# Protoboard_MX4-7-9-ESP12.net
KiCad netlist of a schematic drawn in EAGLE
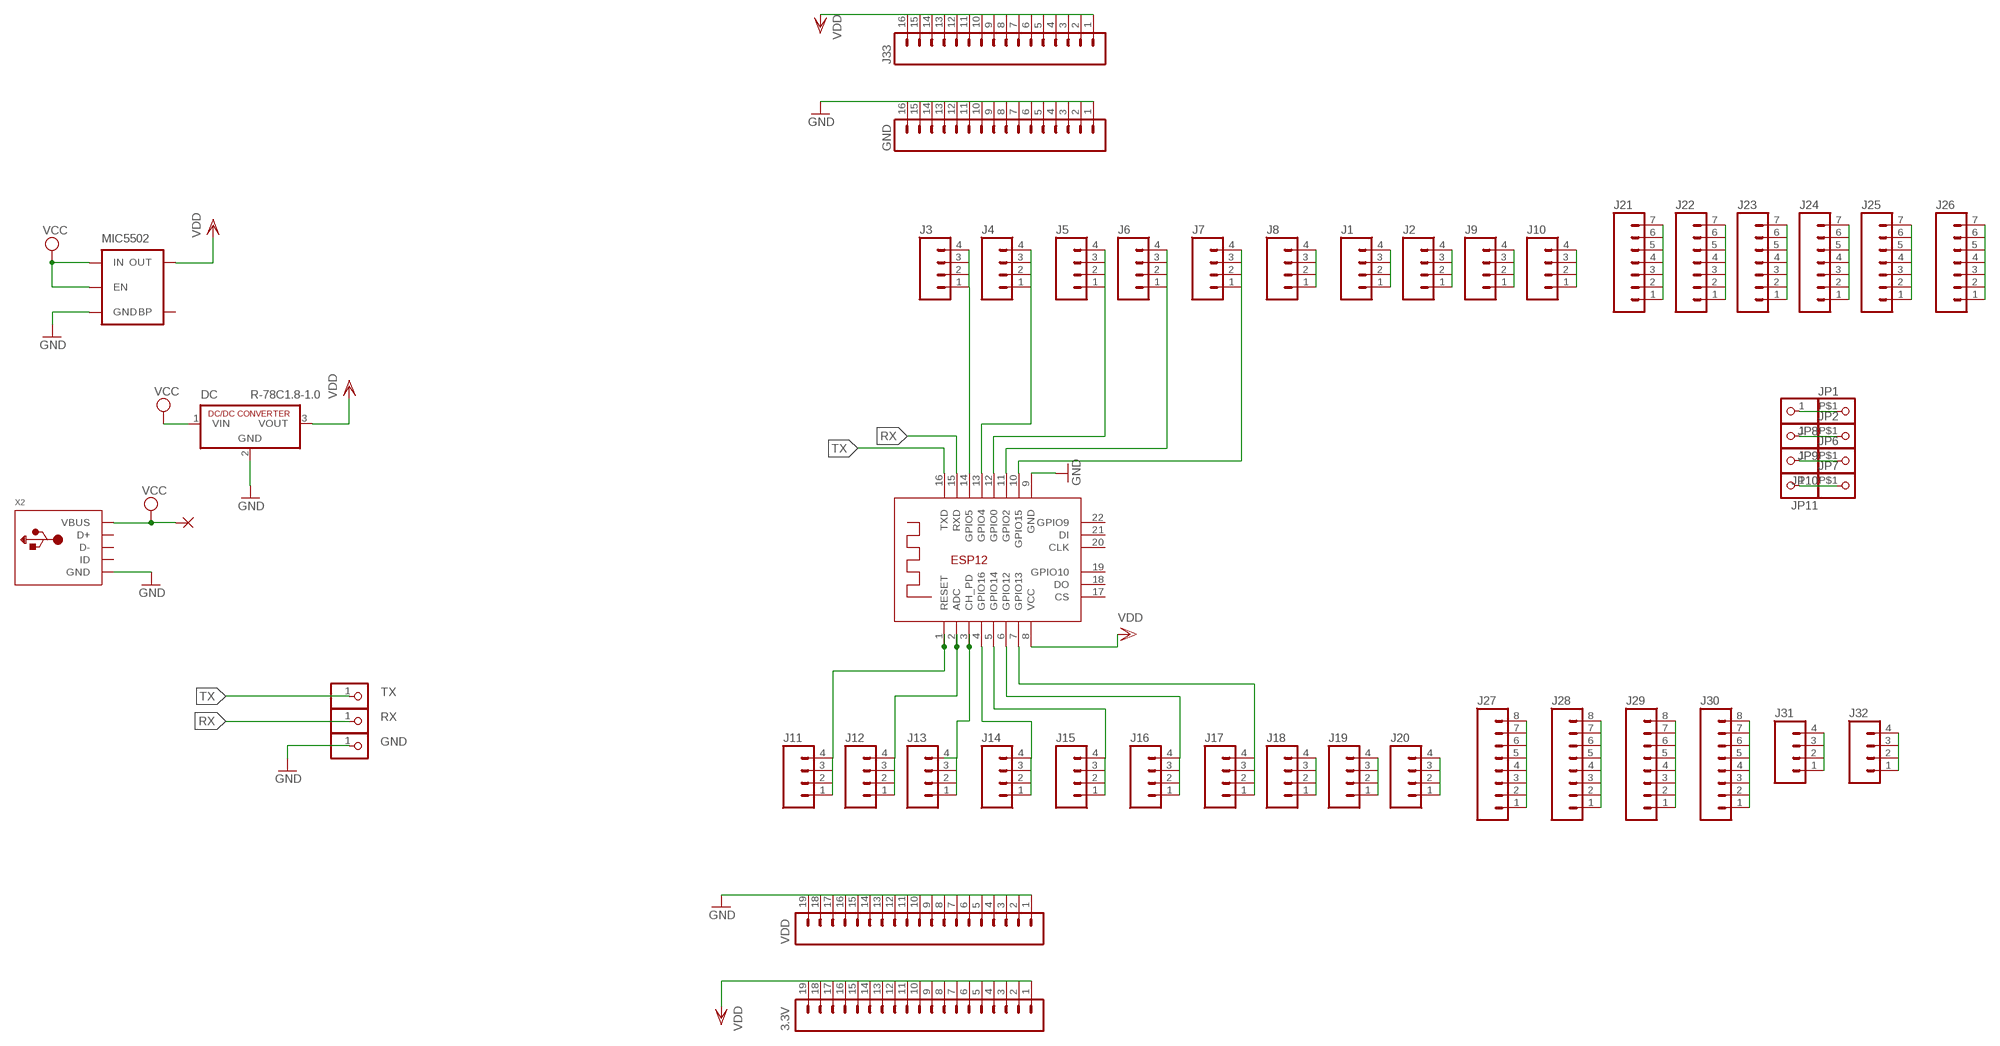
[diagram p0: schematic, sheet 1]

(export (version "E")
  (design (tool "Eeschema 10.0.6"))
  (components
    (comp (ref "3.3V")
      (value "M191X19_NO_SILK")
      (footprint "eagle-import:1X19_NO_SILK")
      (libsource (lib "eagle-import") (part "M191X19_NO_SILK"))
    )
    (comp (ref "5V")
      (value "1,6/0,8")
      (footprint "eagle-import:1,6_0,8")
      (libsource (lib "eagle-import") (part "1,6/0,8"))
    )
    (comp (ref "DC")
      (value "R-78C1.8-1.0")
      (footprint "eagle-import:SIP3")
      (libsource (lib "eagle-import") (part "R-78C-1.01.8"))
    )
    (comp (ref "GND")
      (value "M161X16_NO_SILK")
      (footprint "eagle-import:1X16_NO_SILK")
      (libsource (lib "eagle-import") (part "M161X16_NO_SILK"))
    )
    (comp (ref "J1")
      (value "M04NO_SILK_ALL_ROUND")
      (footprint "eagle-import:1X04_NO_SILK_ALL_ROUND")
      (libsource (lib "eagle-import") (part "M04NO_SILK_ALL_ROUND"))
    )
    (comp (ref "J2")
      (value "M04NO_SILK_ALL_ROUND")
      (footprint "eagle-import:1X04_NO_SILK_ALL_ROUND")
      (libsource (lib "eagle-import") (part "M04NO_SILK_ALL_ROUND"))
    )
    (comp (ref "J3")
      (value "M04NO_SILK_ALL_ROUND")
      (footprint "eagle-import:1X04_NO_SILK_ALL_ROUND")
      (libsource (lib "eagle-import") (part "M04NO_SILK_ALL_ROUND"))
    )
    (comp (ref "J4")
      (value "M04NO_SILK_ALL_ROUND")
      (footprint "eagle-import:1X04_NO_SILK_ALL_ROUND")
      (libsource (lib "eagle-import") (part "M04NO_SILK_ALL_ROUND"))
    )
    (comp (ref "J5")
      (value "M04NO_SILK_ALL_ROUND")
      (footprint "eagle-import:1X04_NO_SILK_ALL_ROUND")
      (libsource (lib "eagle-import") (part "M04NO_SILK_ALL_ROUND"))
    )
    (comp (ref "J6")
      (value "M04NO_SILK_ALL_ROUND")
      (footprint "eagle-import:1X04_NO_SILK_ALL_ROUND")
      (libsource (lib "eagle-import") (part "M04NO_SILK_ALL_ROUND"))
    )
    (comp (ref "J7")
      (value "M04NO_SILK_ALL_ROUND")
      (footprint "eagle-import:1X04_NO_SILK_ALL_ROUND")
      (libsource (lib "eagle-import") (part "M04NO_SILK_ALL_ROUND"))
    )
    (comp (ref "J8")
      (value "M04NO_SILK_ALL_ROUND")
      (footprint "eagle-import:1X04_NO_SILK_ALL_ROUND")
      (libsource (lib "eagle-import") (part "M04NO_SILK_ALL_ROUND"))
    )
    (comp (ref "J9")
      (value "M04NO_SILK_ALL_ROUND")
      (footprint "eagle-import:1X04_NO_SILK_ALL_ROUND")
      (libsource (lib "eagle-import") (part "M04NO_SILK_ALL_ROUND"))
    )
    (comp (ref "J10")
      (value "M04NO_SILK_ALL_ROUND")
      (footprint "eagle-import:1X04_NO_SILK_ALL_ROUND")
      (libsource (lib "eagle-import") (part "M04NO_SILK_ALL_ROUND"))
    )
    (comp (ref "J11")
      (value "M04NO_SILK_ALL_ROUND")
      (footprint "eagle-import:1X04_NO_SILK_ALL_ROUND")
      (libsource (lib "eagle-import") (part "M04NO_SILK_ALL_ROUND"))
    )
    (comp (ref "J12")
      (value "M04NO_SILK_ALL_ROUND")
      (footprint "eagle-import:1X04_NO_SILK_ALL_ROUND")
      (libsource (lib "eagle-import") (part "M04NO_SILK_ALL_ROUND"))
    )
    (comp (ref "J13")
      (value "M04NO_SILK_ALL_ROUND")
      (footprint "eagle-import:1X04_NO_SILK_ALL_ROUND")
      (libsource (lib "eagle-import") (part "M04NO_SILK_ALL_ROUND"))
    )
    (comp (ref "J14")
      (value "M04NO_SILK_ALL_ROUND")
      (footprint "eagle-import:1X04_NO_SILK_ALL_ROUND")
      (libsource (lib "eagle-import") (part "M04NO_SILK_ALL_ROUND"))
    )
    (comp (ref "J15")
      (value "M04NO_SILK_ALL_ROUND")
      (footprint "eagle-import:1X04_NO_SILK_ALL_ROUND")
      (libsource (lib "eagle-import") (part "M04NO_SILK_ALL_ROUND"))
    )
    (comp (ref "J16")
      (value "M04NO_SILK_ALL_ROUND")
      (footprint "eagle-import:1X04_NO_SILK_ALL_ROUND")
      (libsource (lib "eagle-import") (part "M04NO_SILK_ALL_ROUND"))
    )
    (comp (ref "J17")
      (value "M04NO_SILK_ALL_ROUND")
      (footprint "eagle-import:1X04_NO_SILK_ALL_ROUND")
      (libsource (lib "eagle-import") (part "M04NO_SILK_ALL_ROUND"))
    )
    (comp (ref "J18")
      (value "M04NO_SILK_ALL_ROUND")
      (footprint "eagle-import:1X04_NO_SILK_ALL_ROUND")
      (libsource (lib "eagle-import") (part "M04NO_SILK_ALL_ROUND"))
    )
    (comp (ref "J19")
      (value "M04NO_SILK_ALL_ROUND")
      (footprint "eagle-import:1X04_NO_SILK_ALL_ROUND")
      (libsource (lib "eagle-import") (part "M04NO_SILK_ALL_ROUND"))
    )
    (comp (ref "J20")
      (value "M04NO_SILK_ALL_ROUND")
      (footprint "eagle-import:1X04_NO_SILK_ALL_ROUND")
      (libsource (lib "eagle-import") (part "M04NO_SILK_ALL_ROUND"))
    )
    (comp (ref "J21")
      (value "M07NO_SILK")
      (footprint "eagle-import:1X07_NO_SILK")
      (libsource (lib "eagle-import") (part "M07NO_SILK"))
    )
    (comp (ref "J22")
      (value "M07NO_SILK")
      (footprint "eagle-import:1X07_NO_SILK")
      (libsource (lib "eagle-import") (part "M07NO_SILK"))
    )
    (comp (ref "J23")
      (value "M07NO_SILK")
      (footprint "eagle-import:1X07_NO_SILK")
      (libsource (lib "eagle-import") (part "M07NO_SILK"))
    )
    (comp (ref "J24")
      (value "M07NO_SILK")
      (footprint "eagle-import:1X07_NO_SILK")
      (libsource (lib "eagle-import") (part "M07NO_SILK"))
    )
    (comp (ref "J25")
      (value "M07NO_SILK")
      (footprint "eagle-import:1X07_NO_SILK")
      (libsource (lib "eagle-import") (part "M07NO_SILK"))
    )
    (comp (ref "J26")
      (value "M07NO_SILK")
      (footprint "eagle-import:1X07_NO_SILK")
      (libsource (lib "eagle-import") (part "M07NO_SILK"))
    )
    (comp (ref "J27")
      (value "M08NO_SILK_FEMALE_PTH")
      (footprint "eagle-import:1X08_NO_SILK")
      (libsource (lib "eagle-import") (part "M08NO_SILK_FEMALE_PTH"))
    )
    (comp (ref "J28")
      (value "M08NO_SILK_FEMALE_PTH")
      (footprint "eagle-import:1X08_NO_SILK")
      (libsource (lib "eagle-import") (part "M08NO_SILK_FEMALE_PTH"))
    )
    (comp (ref "J29")
      (value "M08NO_SILK_FEMALE_PTH")
      (footprint "eagle-import:1X08_NO_SILK")
      (libsource (lib "eagle-import") (part "M08NO_SILK_FEMALE_PTH"))
    )
    (comp (ref "J30")
      (value "M08NO_SILK_FEMALE_PTH")
      (footprint "eagle-import:1X08_NO_SILK")
      (libsource (lib "eagle-import") (part "M08NO_SILK_FEMALE_PTH"))
    )
    (comp (ref "J31")
      (value "M04NO_SILK_ALL_ROUND")
      (footprint "eagle-import:1X04_NO_SILK_ALL_ROUND")
      (libsource (lib "eagle-import") (part "M04NO_SILK_ALL_ROUND"))
    )
    (comp (ref "J32")
      (value "M04NO_SILK_ALL_ROUND")
      (footprint "eagle-import:1X04_NO_SILK_ALL_ROUND")
      (libsource (lib "eagle-import") (part "M04NO_SILK_ALL_ROUND"))
    )
    (comp (ref "J33")
      (value "M161X16_NO_SILK")
      (footprint "eagle-import:1X16_NO_SILK")
      (libsource (lib "eagle-import") (part "M161X16_NO_SILK"))
    )
    (comp (ref "JP1")
      (value "PINHD-1X1-BIGPOGO")
      (footprint "eagle-import:1X1-BIGPOGO")
      (libsource (lib "eagle-import") (part "PINHD-1X1-BIGPOGO"))
    )
    (comp (ref "JP2")
      (value "PINHD-1X1-BIGPOGO")
      (footprint "eagle-import:1X1-BIGPOGO")
      (libsource (lib "eagle-import") (part "PINHD-1X1-BIGPOGO"))
    )
    (comp (ref "JP3")
      (value "TX")
      (footprint "eagle-import:1X01-CLEANBIG")
      (libsource (lib "eagle-import") (part "PINHD-1X1CB"))
    )
    (comp (ref "JP4")
      (value "RX")
      (footprint "eagle-import:1X01-CLEANBIG")
      (libsource (lib "eagle-import") (part "PINHD-1X1CB"))
    )
    (comp (ref "JP5")
      (value "GND")
      (footprint "eagle-import:1X01-CLEANBIG")
      (libsource (lib "eagle-import") (part "PINHD-1X1CB"))
    )
    (comp (ref "JP6")
      (value "PINHD-1X1-BIGPOGO")
      (footprint "eagle-import:1X1-BIGPOGO")
      (libsource (lib "eagle-import") (part "PINHD-1X1-BIGPOGO"))
    )
    (comp (ref "JP7")
      (value "PINHD-1X1-BIGPOGO")
      (footprint "eagle-import:1X1-BIGPOGO")
      (libsource (lib "eagle-import") (part "PINHD-1X1-BIGPOGO"))
    )
    (comp (ref "JP8")
      (value "PINHD-1X1CB")
      (footprint "eagle-import:1X01-CLEANBIG")
      (libsource (lib "eagle-import") (part "PINHD-1X1CB"))
    )
    (comp (ref "JP9")
      (value "PINHD-1X1CB")
      (footprint "eagle-import:1X01-CLEANBIG")
      (libsource (lib "eagle-import") (part "PINHD-1X1CB"))
    )
    (comp (ref "JP10")
      (value "PINHD-1X1CB")
      (footprint "eagle-import:1X01-CLEANBIG")
      (libsource (lib "eagle-import") (part "PINHD-1X1CB"))
    )
    (comp (ref "JP11")
      (value "PINHD-1X1CB")
      (footprint "eagle-import:1X01-CLEANBIG")
      (libsource (lib "eagle-import") (part "PINHD-1X1CB"))
    )
    (comp (ref "MIC5502")
      (value "MIC52053.3V")
      (footprint "eagle-import:SOT23-5")
      (libsource (lib "eagle-import") (part "MIC52053.3V"))
    )
    (comp (ref "VDD")
      (value "M191X19_NO_SILK")
      (footprint "eagle-import:1X19_NO_SILK")
      (libsource (lib "eagle-import") (part "M191X19_NO_SILK"))
    )
    (comp (ref "X1")
      (value "ESP-12E")
      (footprint "eagle-import:ESP-12E")
      (libsource (lib "eagle-import") (part "ESP-12E"))
    )
    (comp (ref "X2")
      (value "USBMICRO_20329")
      (footprint "eagle-import:4UCONN_20329")
      (libsource (lib "eagle-import") (part "USBMICRO_20329"))
    )
  )
  (nets
    (net (code "1") (name "GND") (class "Default")
      (node (ref "DC") (pin "2") (pinfunction "GND_2") (pintype "passive"))
      (node (ref "GND") (pin "1") (pinfunction "1_1") (pintype "passive"))
      (node (ref "GND") (pin "10") (pinfunction "10_10") (pintype "passive"))
      (node (ref "GND") (pin "11") (pinfunction "11_11") (pintype "passive"))
      (node (ref "GND") (pin "12") (pinfunction "12_12") (pintype "passive"))
      (node (ref "GND") (pin "13") (pinfunction "13_13") (pintype "passive"))
      (node (ref "GND") (pin "14") (pinfunction "14_14") (pintype "passive"))
      (node (ref "GND") (pin "15") (pinfunction "15_15") (pintype "passive"))
      (node (ref "GND") (pin "16") (pinfunction "16_16") (pintype "passive"))
      (node (ref "GND") (pin "2") (pinfunction "2_2") (pintype "passive"))
      (node (ref "GND") (pin "3") (pinfunction "3_3") (pintype "passive"))
      (node (ref "GND") (pin "4") (pinfunction "4_4") (pintype "passive"))
      (node (ref "GND") (pin "5") (pinfunction "5_5") (pintype "passive"))
      (node (ref "GND") (pin "6") (pinfunction "6_6") (pintype "passive"))
      (node (ref "GND") (pin "7") (pinfunction "7_7") (pintype "passive"))
      (node (ref "GND") (pin "8") (pinfunction "8_8") (pintype "passive"))
      (node (ref "GND") (pin "9") (pinfunction "9_9") (pintype "passive"))
      (node (ref "JP5") (pin "1") (pinfunction "1_1") (pintype "passive"))
      (node (ref "MIC5502") (pin "2") (pinfunction "GND_2") (pintype "input"))
      (node (ref "VDD") (pin "1") (pinfunction "1_1") (pintype "passive"))
      (node (ref "VDD") (pin "10") (pinfunction "10_10") (pintype "passive"))
      (node (ref "VDD") (pin "11") (pinfunction "11_11") (pintype "passive"))
      (node (ref "VDD") (pin "12") (pinfunction "12_12") (pintype "passive"))
      (node (ref "VDD") (pin "13") (pinfunction "13_13") (pintype "passive"))
      (node (ref "VDD") (pin "14") (pinfunction "14_14") (pintype "passive"))
      (node (ref "VDD") (pin "15") (pinfunction "15_15") (pintype "passive"))
      (node (ref "VDD") (pin "16") (pinfunction "16_16") (pintype "passive"))
      (node (ref "VDD") (pin "17") (pinfunction "17_17") (pintype "passive"))
      (node (ref "VDD") (pin "18") (pinfunction "18_18") (pintype "passive"))
      (node (ref "VDD") (pin "19") (pinfunction "19_19") (pintype "passive"))
      (node (ref "VDD") (pin "2") (pinfunction "2_2") (pintype "passive"))
      (node (ref "VDD") (pin "3") (pinfunction "3_3") (pintype "passive"))
      (node (ref "VDD") (pin "4") (pinfunction "4_4") (pintype "passive"))
      (node (ref "VDD") (pin "5") (pinfunction "5_5") (pintype "passive"))
      (node (ref "VDD") (pin "6") (pinfunction "6_6") (pintype "passive"))
      (node (ref "VDD") (pin "7") (pinfunction "7_7") (pintype "passive"))
      (node (ref "VDD") (pin "8") (pinfunction "8_8") (pintype "passive"))
      (node (ref "VDD") (pin "9") (pinfunction "9_9") (pintype "passive"))
      (node (ref "X1") (pin "9") (pinfunction "GND_9") (pintype "power_in"))
      (node (ref "X2") (pin "BASE@1") (pinfunction "GND_BASE@1") (pintype "power_in"))
      (node (ref "X2") (pin "BASE@2") (pinfunction "GND_BASE@2") (pintype "power_in"))
      (node (ref "X2") (pin "GND") (pinfunction "GND_GND") (pintype "power_in"))
      (node (ref "X2") (pin "SPRT@1") (pinfunction "GND_SPRT@1") (pintype "power_in"))
      (node (ref "X2") (pin "SPRT@2") (pinfunction "GND_SPRT@2") (pintype "power_in"))
      (node (ref "X2") (pin "SPRT@3") (pinfunction "GND_SPRT@3") (pintype "power_in"))
      (node (ref "X2") (pin "SPRT@4") (pinfunction "GND_SPRT@4") (pintype "power_in"))
    )
    (net (code "2") (name "Net-(J1-Pad1)") (class "Default")
      (node (ref "J1") (pin "1") (pinfunction "1_1") (pintype "passive"))
      (node (ref "J1") (pin "2") (pinfunction "2_2") (pintype "passive"))
      (node (ref "J1") (pin "3") (pinfunction "3_3") (pintype "passive"))
      (node (ref "J1") (pin "4") (pinfunction "4_4") (pintype "passive"))
    )
    (net (code "3") (name "Net-(J2-Pad1)") (class "Default")
      (node (ref "J2") (pin "1") (pinfunction "1_1") (pintype "passive"))
      (node (ref "J2") (pin "2") (pinfunction "2_2") (pintype "passive"))
      (node (ref "J2") (pin "3") (pinfunction "3_3") (pintype "passive"))
      (node (ref "J2") (pin "4") (pinfunction "4_4") (pintype "passive"))
    )
    (net (code "4") (name "Net-(J8-Pad1)") (class "Default")
      (node (ref "J8") (pin "1") (pinfunction "1_1") (pintype "passive"))
      (node (ref "J8") (pin "2") (pinfunction "2_2") (pintype "passive"))
      (node (ref "J8") (pin "3") (pinfunction "3_3") (pintype "passive"))
      (node (ref "J8") (pin "4") (pinfunction "4_4") (pintype "passive"))
    )
    (net (code "5") (name "Net-(J9-Pad1)") (class "Default")
      (node (ref "J9") (pin "1") (pinfunction "1_1") (pintype "passive"))
      (node (ref "J9") (pin "2") (pinfunction "2_2") (pintype "passive"))
      (node (ref "J9") (pin "3") (pinfunction "3_3") (pintype "passive"))
      (node (ref "J9") (pin "4") (pinfunction "4_4") (pintype "passive"))
    )
    (net (code "6") (name "Net-(J10-Pad1)") (class "Default")
      (node (ref "J10") (pin "1") (pinfunction "1_1") (pintype "passive"))
      (node (ref "J10") (pin "2") (pinfunction "2_2") (pintype "passive"))
      (node (ref "J10") (pin "3") (pinfunction "3_3") (pintype "passive"))
      (node (ref "J10") (pin "4") (pinfunction "4_4") (pintype "passive"))
    )
    (net (code "7") (name "Net-(J18-Pad1)") (class "Default")
      (node (ref "J18") (pin "1") (pinfunction "1_1") (pintype "passive"))
      (node (ref "J18") (pin "2") (pinfunction "2_2") (pintype "passive"))
      (node (ref "J18") (pin "3") (pinfunction "3_3") (pintype "passive"))
      (node (ref "J18") (pin "4") (pinfunction "4_4") (pintype "passive"))
    )
    (net (code "8") (name "Net-(J19-Pad1)") (class "Default")
      (node (ref "J19") (pin "1") (pinfunction "1_1") (pintype "passive"))
      (node (ref "J19") (pin "2") (pinfunction "2_2") (pintype "passive"))
      (node (ref "J19") (pin "3") (pinfunction "3_3") (pintype "passive"))
      (node (ref "J19") (pin "4") (pinfunction "4_4") (pintype "passive"))
    )
    (net (code "9") (name "Net-(J20-Pad1)") (class "Default")
      (node (ref "J20") (pin "1") (pinfunction "1_1") (pintype "passive"))
      (node (ref "J20") (pin "2") (pinfunction "2_2") (pintype "passive"))
      (node (ref "J20") (pin "3") (pinfunction "3_3") (pintype "passive"))
      (node (ref "J20") (pin "4") (pinfunction "4_4") (pintype "passive"))
    )
    (net (code "10") (name "Net-(J21-Pad1)") (class "Default")
      (node (ref "J21") (pin "1") (pinfunction "1_1") (pintype "passive"))
      (node (ref "J21") (pin "2") (pinfunction "2_2") (pintype "passive"))
      (node (ref "J21") (pin "3") (pinfunction "3_3") (pintype "passive"))
      (node (ref "J21") (pin "4") (pinfunction "4_4") (pintype "passive"))
      (node (ref "J21") (pin "5") (pinfunction "5_5") (pintype "passive"))
      (node (ref "J21") (pin "6") (pinfunction "6_6") (pintype "passive"))
      (node (ref "J21") (pin "7") (pinfunction "7_7") (pintype "passive"))
    )
    (net (code "11") (name "Net-(J22-Pad1)") (class "Default")
      (node (ref "J22") (pin "1") (pinfunction "1_1") (pintype "passive"))
      (node (ref "J22") (pin "2") (pinfunction "2_2") (pintype "passive"))
      (node (ref "J22") (pin "3") (pinfunction "3_3") (pintype "passive"))
      (node (ref "J22") (pin "4") (pinfunction "4_4") (pintype "passive"))
      (node (ref "J22") (pin "5") (pinfunction "5_5") (pintype "passive"))
      (node (ref "J22") (pin "6") (pinfunction "6_6") (pintype "passive"))
      (node (ref "J22") (pin "7") (pinfunction "7_7") (pintype "passive"))
    )
    (net (code "12") (name "Net-(J23-Pad1)") (class "Default")
      (node (ref "J23") (pin "1") (pinfunction "1_1") (pintype "passive"))
      (node (ref "J23") (pin "2") (pinfunction "2_2") (pintype "passive"))
      (node (ref "J23") (pin "3") (pinfunction "3_3") (pintype "passive"))
      (node (ref "J23") (pin "4") (pinfunction "4_4") (pintype "passive"))
      (node (ref "J23") (pin "5") (pinfunction "5_5") (pintype "passive"))
      (node (ref "J23") (pin "6") (pinfunction "6_6") (pintype "passive"))
      (node (ref "J23") (pin "7") (pinfunction "7_7") (pintype "passive"))
    )
    (net (code "13") (name "Net-(J24-Pad1)") (class "Default")
      (node (ref "J24") (pin "1") (pinfunction "1_1") (pintype "passive"))
      (node (ref "J24") (pin "2") (pinfunction "2_2") (pintype "passive"))
      (node (ref "J24") (pin "3") (pinfunction "3_3") (pintype "passive"))
      (node (ref "J24") (pin "4") (pinfunction "4_4") (pintype "passive"))
      (node (ref "J24") (pin "5") (pinfunction "5_5") (pintype "passive"))
      (node (ref "J24") (pin "6") (pinfunction "6_6") (pintype "passive"))
      (node (ref "J24") (pin "7") (pinfunction "7_7") (pintype "passive"))
    )
    (net (code "14") (name "Net-(J25-Pad1)") (class "Default")
      (node (ref "J25") (pin "1") (pinfunction "1_1") (pintype "passive"))
      (node (ref "J25") (pin "2") (pinfunction "2_2") (pintype "passive"))
      (node (ref "J25") (pin "3") (pinfunction "3_3") (pintype "passive"))
      (node (ref "J25") (pin "4") (pinfunction "4_4") (pintype "passive"))
      (node (ref "J25") (pin "5") (pinfunction "5_5") (pintype "passive"))
      (node (ref "J25") (pin "6") (pinfunction "6_6") (pintype "passive"))
      (node (ref "J25") (pin "7") (pinfunction "7_7") (pintype "passive"))
    )
    (net (code "15") (name "Net-(J26-Pad1)") (class "Default")
      (node (ref "J26") (pin "1") (pinfunction "1_1") (pintype "passive"))
      (node (ref "J26") (pin "2") (pinfunction "2_2") (pintype "passive"))
      (node (ref "J26") (pin "3") (pinfunction "3_3") (pintype "passive"))
      (node (ref "J26") (pin "4") (pinfunction "4_4") (pintype "passive"))
      (node (ref "J26") (pin "5") (pinfunction "5_5") (pintype "passive"))
      (node (ref "J26") (pin "6") (pinfunction "6_6") (pintype "passive"))
      (node (ref "J26") (pin "7") (pinfunction "7_7") (pintype "passive"))
    )
    (net (code "16") (name "Net-(J27-Pad1)") (class "Default")
      (node (ref "J27") (pin "1") (pinfunction "1_1") (pintype "passive"))
      (node (ref "J27") (pin "2") (pinfunction "2_2") (pintype "passive"))
      (node (ref "J27") (pin "3") (pinfunction "3_3") (pintype "passive"))
      (node (ref "J27") (pin "4") (pinfunction "4_4") (pintype "passive"))
      (node (ref "J27") (pin "5") (pinfunction "5_5") (pintype "passive"))
      (node (ref "J27") (pin "6") (pinfunction "6_6") (pintype "passive"))
      (node (ref "J27") (pin "7") (pinfunction "7_7") (pintype "passive"))
      (node (ref "J27") (pin "8") (pinfunction "8_8") (pintype "passive"))
    )
    (net (code "17") (name "Net-(J28-Pad1)") (class "Default")
      (node (ref "J28") (pin "1") (pinfunction "1_1") (pintype "passive"))
      (node (ref "J28") (pin "2") (pinfunction "2_2") (pintype "passive"))
      (node (ref "J28") (pin "3") (pinfunction "3_3") (pintype "passive"))
      (node (ref "J28") (pin "4") (pinfunction "4_4") (pintype "passive"))
      (node (ref "J28") (pin "5") (pinfunction "5_5") (pintype "passive"))
      (node (ref "J28") (pin "6") (pinfunction "6_6") (pintype "passive"))
      (node (ref "J28") (pin "7") (pinfunction "7_7") (pintype "passive"))
      (node (ref "J28") (pin "8") (pinfunction "8_8") (pintype "passive"))
    )
    (net (code "18") (name "Net-(J29-Pad1)") (class "Default")
      (node (ref "J29") (pin "1") (pinfunction "1_1") (pintype "passive"))
      (node (ref "J29") (pin "2") (pinfunction "2_2") (pintype "passive"))
      (node (ref "J29") (pin "3") (pinfunction "3_3") (pintype "passive"))
      (node (ref "J29") (pin "4") (pinfunction "4_4") (pintype "passive"))
      (node (ref "J29") (pin "5") (pinfunction "5_5") (pintype "passive"))
      (node (ref "J29") (pin "6") (pinfunction "6_6") (pintype "passive"))
      (node (ref "J29") (pin "7") (pinfunction "7_7") (pintype "passive"))
      (node (ref "J29") (pin "8") (pinfunction "8_8") (pintype "passive"))
    )
    (net (code "19") (name "Net-(J30-Pad1)") (class "Default")
      (node (ref "J30") (pin "1") (pinfunction "1_1") (pintype "passive"))
      (node (ref "J30") (pin "2") (pinfunction "2_2") (pintype "passive"))
      (node (ref "J30") (pin "3") (pinfunction "3_3") (pintype "passive"))
      (node (ref "J30") (pin "4") (pinfunction "4_4") (pintype "passive"))
      (node (ref "J30") (pin "5") (pinfunction "5_5") (pintype "passive"))
      (node (ref "J30") (pin "6") (pinfunction "6_6") (pintype "passive"))
      (node (ref "J30") (pin "7") (pinfunction "7_7") (pintype "passive"))
      (node (ref "J30") (pin "8") (pinfunction "8_8") (pintype "passive"))
    )
    (net (code "20") (name "Net-(J31-Pad1)") (class "Default")
      (node (ref "J31") (pin "1") (pinfunction "1_1") (pintype "passive"))
      (node (ref "J31") (pin "2") (pinfunction "2_2") (pintype "passive"))
      (node (ref "J31") (pin "3") (pinfunction "3_3") (pintype "passive"))
      (node (ref "J31") (pin "4") (pinfunction "4_4") (pintype "passive"))
    )
    (net (code "21") (name "Net-(J32-Pad1)") (class "Default")
      (node (ref "J32") (pin "1") (pinfunction "1_1") (pintype "passive"))
      (node (ref "J32") (pin "2") (pinfunction "2_2") (pintype "passive"))
      (node (ref "J32") (pin "3") (pinfunction "3_3") (pintype "passive"))
      (node (ref "J32") (pin "4") (pinfunction "4_4") (pintype "passive"))
    )
    (net (code "22") (name "Net-(JP1-1)") (class "Default")
      (node (ref "JP1") (pin "P$1") (pinfunction "1_P$1") (pintype "passive"))
      (node (ref "JP8") (pin "1") (pinfunction "1_1") (pintype "passive"))
    )
    (net (code "23") (name "Net-(JP2-1)") (class "Default")
      (node (ref "JP2") (pin "P$1") (pinfunction "1_P$1") (pintype "passive"))
      (node (ref "JP9") (pin "1") (pinfunction "1_1") (pintype "passive"))
    )
    (net (code "24") (name "Net-(JP6-1)") (class "Default")
      (node (ref "JP10") (pin "1") (pinfunction "1_1") (pintype "passive"))
      (node (ref "JP6") (pin "P$1") (pinfunction "1_P$1") (pintype "passive"))
    )
    (net (code "25") (name "Net-(JP7-1)") (class "Default")
      (node (ref "JP11") (pin "1") (pinfunction "1_1") (pintype "passive"))
      (node (ref "JP7") (pin "P$1") (pinfunction "1_P$1") (pintype "passive"))
    )
    (net (code "26") (name "Net-(X1-ADC)") (class "Default")
      (node (ref "J12") (pin "1") (pinfunction "1_1") (pintype "passive"))
      (node (ref "J12") (pin "2") (pinfunction "2_2") (pintype "passive"))
      (node (ref "J12") (pin "3") (pinfunction "3_3") (pintype "passive"))
      (node (ref "J12") (pin "4") (pinfunction "4_4") (pintype "passive"))
      (node (ref "X1") (pin "2") (pinfunction "ADC_2") (pintype "passive"))
    )
    (net (code "27") (name "Net-(X1-CH_PD)") (class "Default")
      (node (ref "J13") (pin "1") (pinfunction "1_1") (pintype "passive"))
      (node (ref "J13") (pin "2") (pinfunction "2_2") (pintype "passive"))
      (node (ref "J13") (pin "3") (pinfunction "3_3") (pintype "passive"))
      (node (ref "J13") (pin "4") (pinfunction "4_4") (pintype "passive"))
      (node (ref "X1") (pin "3") (pinfunction "CH_PD_3") (pintype "input"))
    )
    (net (code "28") (name "Net-(X1-GPIO0)") (class "Default")
      (node (ref "J5") (pin "1") (pinfunction "1_1") (pintype "passive"))
      (node (ref "J5") (pin "2") (pinfunction "2_2") (pintype "passive"))
      (node (ref "J5") (pin "3") (pinfunction "3_3") (pintype "passive"))
      (node (ref "J5") (pin "4") (pinfunction "4_4") (pintype "passive"))
      (node (ref "X1") (pin "12") (pinfunction "GPIO0_12") (pintype "bidirectional"))
    )
    (net (code "29") (name "Net-(X1-GPIO2)") (class "Default")
      (node (ref "J6") (pin "1") (pinfunction "1_1") (pintype "passive"))
      (node (ref "J6") (pin "2") (pinfunction "2_2") (pintype "passive"))
      (node (ref "J6") (pin "3") (pinfunction "3_3") (pintype "passive"))
      (node (ref "J6") (pin "4") (pinfunction "4_4") (pintype "passive"))
      (node (ref "X1") (pin "11") (pinfunction "GPIO2_11") (pintype "bidirectional"))
    )
    (net (code "30") (name "Net-(X1-GPIO4)") (class "Default")
      (node (ref "J4") (pin "1") (pinfunction "1_1") (pintype "passive"))
      (node (ref "J4") (pin "2") (pinfunction "2_2") (pintype "passive"))
      (node (ref "J4") (pin "3") (pinfunction "3_3") (pintype "passive"))
      (node (ref "J4") (pin "4") (pinfunction "4_4") (pintype "passive"))
      (node (ref "X1") (pin "13") (pinfunction "GPIO4_13") (pintype "bidirectional"))
    )
    (net (code "31") (name "Net-(X1-GPIO5)") (class "Default")
      (node (ref "J3") (pin "1") (pinfunction "1_1") (pintype "passive"))
      (node (ref "J3") (pin "2") (pinfunction "2_2") (pintype "passive"))
      (node (ref "J3") (pin "3") (pinfunction "3_3") (pintype "passive"))
      (node (ref "J3") (pin "4") (pinfunction "4_4") (pintype "passive"))
      (node (ref "X1") (pin "14") (pinfunction "GPIO5_14") (pintype "bidirectional"))
    )
    (net (code "32") (name "Net-(X1-GPIO12)") (class "Default")
      (node (ref "J16") (pin "1") (pinfunction "1_1") (pintype "passive"))
      (node (ref "J16") (pin "2") (pinfunction "2_2") (pintype "passive"))
      (node (ref "J16") (pin "3") (pinfunction "3_3") (pintype "passive"))
      (node (ref "J16") (pin "4") (pinfunction "4_4") (pintype "passive"))
      (node (ref "X1") (pin "6") (pinfunction "GPIO12_6") (pintype "bidirectional"))
    )
    (net (code "33") (name "Net-(X1-GPIO13)") (class "Default")
      (node (ref "J17") (pin "1") (pinfunction "1_1") (pintype "passive"))
      (node (ref "J17") (pin "2") (pinfunction "2_2") (pintype "passive"))
      (node (ref "J17") (pin "3") (pinfunction "3_3") (pintype "passive"))
      (node (ref "J17") (pin "4") (pinfunction "4_4") (pintype "passive"))
      (node (ref "X1") (pin "7") (pinfunction "GPIO13_7") (pintype "bidirectional"))
    )
    (net (code "34") (name "Net-(X1-GPIO14)") (class "Default")
      (node (ref "J15") (pin "1") (pinfunction "1_1") (pintype "passive"))
      (node (ref "J15") (pin "2") (pinfunction "2_2") (pintype "passive"))
      (node (ref "J15") (pin "3") (pinfunction "3_3") (pintype "passive"))
      (node (ref "J15") (pin "4") (pinfunction "4_4") (pintype "passive"))
      (node (ref "X1") (pin "5") (pinfunction "GPIO14_5") (pintype "bidirectional"))
    )
    (net (code "35") (name "Net-(X1-GPIO15)") (class "Default")
      (node (ref "J7") (pin "1") (pinfunction "1_1") (pintype "passive"))
      (node (ref "J7") (pin "2") (pinfunction "2_2") (pintype "passive"))
      (node (ref "J7") (pin "3") (pinfunction "3_3") (pintype "passive"))
      (node (ref "J7") (pin "4") (pinfunction "4_4") (pintype "passive"))
      (node (ref "X1") (pin "10") (pinfunction "GPIO15_10") (pintype "bidirectional"))
    )
    (net (code "36") (name "Net-(X1-GPIO16)") (class "Default")
      (node (ref "J14") (pin "1") (pinfunction "1_1") (pintype "passive"))
      (node (ref "J14") (pin "2") (pinfunction "2_2") (pintype "passive"))
      (node (ref "J14") (pin "3") (pinfunction "3_3") (pintype "passive"))
      (node (ref "J14") (pin "4") (pinfunction "4_4") (pintype "passive"))
      (node (ref "X1") (pin "4") (pinfunction "GPIO16_4") (pintype "bidirectional"))
    )
    (net (code "37") (name "Net-(X1-RESET)") (class "Default")
      (node (ref "J11") (pin "1") (pinfunction "1_1") (pintype "passive"))
      (node (ref "J11") (pin "2") (pinfunction "2_2") (pintype "passive"))
      (node (ref "J11") (pin "3") (pinfunction "3_3") (pintype "passive"))
      (node (ref "J11") (pin "4") (pinfunction "4_4") (pintype "passive"))
      (node (ref "X1") (pin "1") (pinfunction "RESET_1") (pintype "input"))
    )
    (net (code "38") (name "RX") (class "Default")
      (node (ref "JP4") (pin "1") (pinfunction "1_1") (pintype "passive"))
      (node (ref "X1") (pin "15") (pinfunction "RXD_15") (pintype "input"))
    )
    (net (code "39") (name "TX") (class "Default")
      (node (ref "JP3") (pin "1") (pinfunction "1_1") (pintype "passive"))
      (node (ref "X1") (pin "16") (pinfunction "TXD_16") (pintype "output"))
    )
    (net (code "40") (name "VCC") (class "Default")
      (node (ref "5V") (pin "1") (pinfunction "P_1") (pintype "passive"))
      (node (ref "DC") (pin "1") (pinfunction "VIN_1") (pintype "passive"))
      (node (ref "MIC5502") (pin "1") (pinfunction "IN_1") (pintype "input"))
      (node (ref "MIC5502") (pin "3") (pinfunction "EN_3") (pintype "input"))
      (node (ref "X2") (pin "VBUS") (pinfunction "VBUS_VBUS") (pintype "power_in"))
    )
    (net (code "41") (name "VDD") (class "Default")
      (node (ref "3.3V") (pin "1") (pinfunction "1_1") (pintype "passive"))
      (node (ref "3.3V") (pin "10") (pinfunction "10_10") (pintype "passive"))
      (node (ref "3.3V") (pin "11") (pinfunction "11_11") (pintype "passive"))
      (node (ref "3.3V") (pin "12") (pinfunction "12_12") (pintype "passive"))
      (node (ref "3.3V") (pin "13") (pinfunction "13_13") (pintype "passive"))
      (node (ref "3.3V") (pin "14") (pinfunction "14_14") (pintype "passive"))
      (node (ref "3.3V") (pin "15") (pinfunction "15_15") (pintype "passive"))
      (node (ref "3.3V") (pin "16") (pinfunction "16_16") (pintype "passive"))
      (node (ref "3.3V") (pin "17") (pinfunction "17_17") (pintype "passive"))
      (node (ref "3.3V") (pin "18") (pinfunction "18_18") (pintype "passive"))
      (node (ref "3.3V") (pin "19") (pinfunction "19_19") (pintype "passive"))
      (node (ref "3.3V") (pin "2") (pinfunction "2_2") (pintype "passive"))
      (node (ref "3.3V") (pin "3") (pinfunction "3_3") (pintype "passive"))
      (node (ref "3.3V") (pin "4") (pinfunction "4_4") (pintype "passive"))
      (node (ref "3.3V") (pin "5") (pinfunction "5_5") (pintype "passive"))
      (node (ref "3.3V") (pin "6") (pinfunction "6_6") (pintype "passive"))
      (node (ref "3.3V") (pin "7") (pinfunction "7_7") (pintype "passive"))
      (node (ref "3.3V") (pin "8") (pinfunction "8_8") (pintype "passive"))
      (node (ref "3.3V") (pin "9") (pinfunction "9_9") (pintype "passive"))
      (node (ref "DC") (pin "3") (pinfunction "VOUT_3") (pintype "passive"))
      (node (ref "J33") (pin "1") (pinfunction "1_1") (pintype "passive"))
      (node (ref "J33") (pin "10") (pinfunction "10_10") (pintype "passive"))
      (node (ref "J33") (pin "11") (pinfunction "11_11") (pintype "passive"))
      (node (ref "J33") (pin "12") (pinfunction "12_12") (pintype "passive"))
      (node (ref "J33") (pin "13") (pinfunction "13_13") (pintype "passive"))
      (node (ref "J33") (pin "14") (pinfunction "14_14") (pintype "passive"))
      (node (ref "J33") (pin "15") (pinfunction "15_15") (pintype "passive"))
      (node (ref "J33") (pin "16") (pinfunction "16_16") (pintype "passive"))
      (node (ref "J33") (pin "2") (pinfunction "2_2") (pintype "passive"))
      (node (ref "J33") (pin "3") (pinfunction "3_3") (pintype "passive"))
      (node (ref "J33") (pin "4") (pinfunction "4_4") (pintype "passive"))
      (node (ref "J33") (pin "5") (pinfunction "5_5") (pintype "passive"))
      (node (ref "J33") (pin "6") (pinfunction "6_6") (pintype "passive"))
      (node (ref "J33") (pin "7") (pinfunction "7_7") (pintype "passive"))
      (node (ref "J33") (pin "8") (pinfunction "8_8") (pintype "passive"))
      (node (ref "J33") (pin "9") (pinfunction "9_9") (pintype "passive"))
      (node (ref "MIC5502") (pin "5") (pinfunction "OUT_5") (pintype "passive"))
      (node (ref "X1") (pin "8") (pinfunction "VCC_8") (pintype "power_in"))
    )
    (net (code "42") (name "unconnected-(MIC5502-BP-Pad4)") (class "Default")
      (node (ref "MIC5502") (pin "4") (pinfunction "BP_4") (pintype "input"))
    )
    (net (code "43") (name "unconnected-(X1-CLK-Pad20)") (class "Default")
      (node (ref "X1") (pin "20") (pinfunction "CLK_20") (pintype "bidirectional"))
    )
    (net (code "44") (name "unconnected-(X1-CS-Pad17)") (class "Default")
      (node (ref "X1") (pin "17") (pinfunction "CS_17") (pintype "bidirectional"))
    )
    (net (code "45") (name "unconnected-(X1-DI-Pad21)") (class "Default")
      (node (ref "X1") (pin "21") (pinfunction "DI_21") (pintype "bidirectional"))
    )
    (net (code "46") (name "unconnected-(X1-DO-Pad18)") (class "Default")
      (node (ref "X1") (pin "18") (pinfunction "DO_18") (pintype "bidirectional"))
    )
    (net (code "47") (name "unconnected-(X1-GPIO9-Pad22)") (class "Default")
      (node (ref "X1") (pin "22") (pinfunction "GPIO9_22") (pintype "bidirectional"))
    )
    (net (code "48") (name "unconnected-(X1-GPIO10-Pad19)") (class "Default")
      (node (ref "X1") (pin "19") (pinfunction "GPIO10_19") (pintype "bidirectional"))
    )
    (net (code "49") (name "unconnected-(X2-PadD+)") (class "Default")
      (node (ref "X2") (pin "D+") (pinfunction "D+_D+") (pintype "bidirectional"))
    )
    (net (code "50") (name "unconnected-(X2-PadD-)") (class "Default")
      (node (ref "X2") (pin "D-") (pinfunction "D-_D-") (pintype "bidirectional"))
    )
    (net (code "51") (name "unconnected-(X2-PadID)") (class "Default")
      (node (ref "X2") (pin "ID") (pinfunction "ID_ID") (pintype "bidirectional"))
    )
  )
)
